# SHDN-CURRENT-S07-V00-LEMInterface.net
KiCad netlist of a schematic drawn in Altium Designer
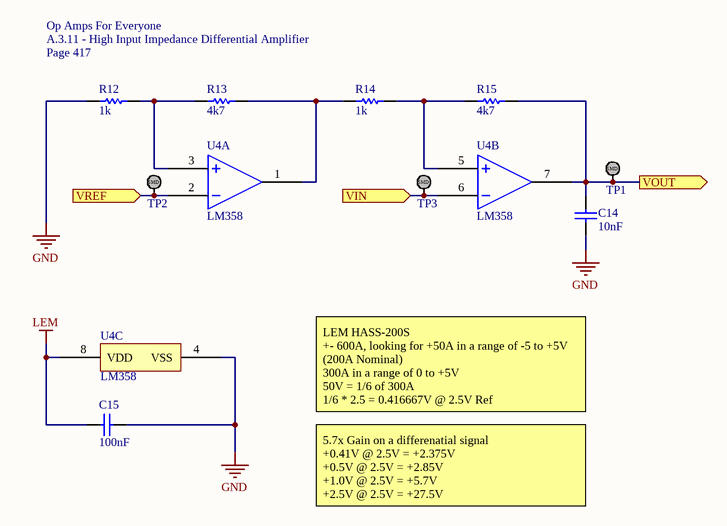
[diagram p0: SHDN-CURRENT-S07-V00-LEMInterface.SchDoc]

(export (version "E")
  (design (tool "Eeschema 10.0.6"))
  (components
    (comp (ref "C14")
      (value "10nF")
      (footprint "Cap_Ceramic_0603")
      (description "Capacitor, Ceramic, SMD, 10nF, 50V, 5%, X7R, 0603")
      (libsource (lib "StandardCapacitors") (part "10nF 50V 5% X7R 0603"))
    )
    (comp (ref "C15")
      (value "100nF")
      (footprint "Cap_Ceramic_0603")
      (description "Capacitor, Ceramic, SMD, 100nF, 50V, 5%, X7R, 0603")
      (libsource (lib "StandardCapacitors") (part "100nF 50V 5% X7R 0603"))
    )
    (comp (ref "R12")
      (value "1k")
      (footprint "Res_ThinFilm_0603")
      (description "Resistor, SMD, 1k, 0.1W, 5%, 0603")
      (libsource (lib "StandardResistors") (part "1k 5% 0603"))
    )
    (comp (ref "R13")
      (value "4k7")
      (footprint "Res_ThinFilm_0603")
      (description "Resistor, SMD, 4k7, 0.1W, 5%, 0603")
      (libsource (lib "StandardResistors") (part "4k7 5% 0603"))
    )
    (comp (ref "R14")
      (value "1k")
      (footprint "Res_ThinFilm_0603")
      (description "Resistor, SMD, 1k, 0.1W, 5%, 0603")
      (libsource (lib "StandardResistors") (part "1k 5% 0603"))
    )
    (comp (ref "R15")
      (value "4k7")
      (footprint "Res_ThinFilm_0603")
      (description "Resistor, SMD, 4k7, 0.1W, 5%, 0603")
      (libsource (lib "StandardResistors") (part "4k7 5% 0603"))
    )
    (comp (ref "TP1")
      (value "TestPoint_SMD")
      (footprint "TestPointSMD")
      (libsource (lib "StandardTest") (part "TestPoint_SMD"))
    )
    (comp (ref "TP2")
      (value "TestPoint_SMD")
      (footprint "TestPointSMD")
      (libsource (lib "StandardTest") (part "TestPoint_SMD"))
    )
    (comp (ref "TP3")
      (value "TestPoint_SMD")
      (footprint "TestPointSMD")
      (libsource (lib "StandardTest") (part "TestPoint_SMD"))
    )
    (comp (ref "U4")
      (value "LM358")
      (footprint "TSSOP-8")
      (description "General Purpose Amplifier 2 Circuit 8-SOIC")
      (libsource (lib "QUTMS_OpAmpLibrary") (part "LM358"))
    )
  )
  (nets
    (net (code "1") (name "/VIN") (class "Default")
      (node (ref "TP3") (pin "1") (pinfunction "1_1") (pintype "passive"))
      (node (ref "U4") (pin "6") (pinfunction "IN2-_6") (pintype "passive"))
    )
    (net (code "2") (name "/VOUT") (class "Default")
      (node (ref "C14") (pin "2") (pinfunction "2_2") (pintype "passive"))
      (node (ref "R15") (pin "2") (pinfunction "2_2") (pintype "passive"))
      (node (ref "TP1") (pin "1") (pinfunction "1_1") (pintype "passive"))
      (node (ref "U4") (pin "7") (pinfunction "OUT1_7") (pintype "passive"))
    )
    (net (code "3") (name "/VREF") (class "Default")
      (node (ref "TP2") (pin "1") (pinfunction "1_1") (pintype "passive"))
      (node (ref "U4") (pin "2") (pinfunction "IN1-_2") (pintype "passive"))
    )
    (net (code "4") (name "GND") (class "Default")
      (node (ref "C14") (pin "1") (pinfunction "1_1") (pintype "passive"))
      (node (ref "C15") (pin "2") (pinfunction "2_2") (pintype "passive"))
      (node (ref "R12") (pin "1") (pinfunction "1_1") (pintype "passive"))
      (node (ref "U4") (pin "4") (pinfunction "VSS_4") (pintype "passive"))
    )
    (net (code "5") (name "LEM") (class "Default")
      (node (ref "C15") (pin "1") (pinfunction "1_1") (pintype "passive"))
      (node (ref "U4") (pin "8") (pinfunction "VDD_8") (pintype "passive"))
    )
    (net (code "6") (name "Net-(U4A-IN1+)") (class "Default")
      (node (ref "R12") (pin "2") (pinfunction "2_2") (pintype "passive"))
      (node (ref "R13") (pin "1") (pinfunction "1_1") (pintype "passive"))
      (node (ref "U4") (pin "3") (pinfunction "IN1+_3") (pintype "passive"))
    )
    (net (code "7") (name "Net-(U4A-OUT1)") (class "Default")
      (node (ref "R13") (pin "2") (pinfunction "2_2") (pintype "passive"))
      (node (ref "R14") (pin "1") (pinfunction "1_1") (pintype "passive"))
      (node (ref "U4") (pin "1") (pinfunction "OUT1_1") (pintype "passive"))
    )
    (net (code "8") (name "Net-(U4B-IN2+)") (class "Default")
      (node (ref "R14") (pin "2") (pinfunction "2_2") (pintype "passive"))
      (node (ref "R15") (pin "1") (pinfunction "1_1") (pintype "passive"))
      (node (ref "U4") (pin "5") (pinfunction "IN2+_5") (pintype "passive"))
    )
  )
)
